# alcoholsensor.net
KiCad netlist of a schematic drawn in EAGLE
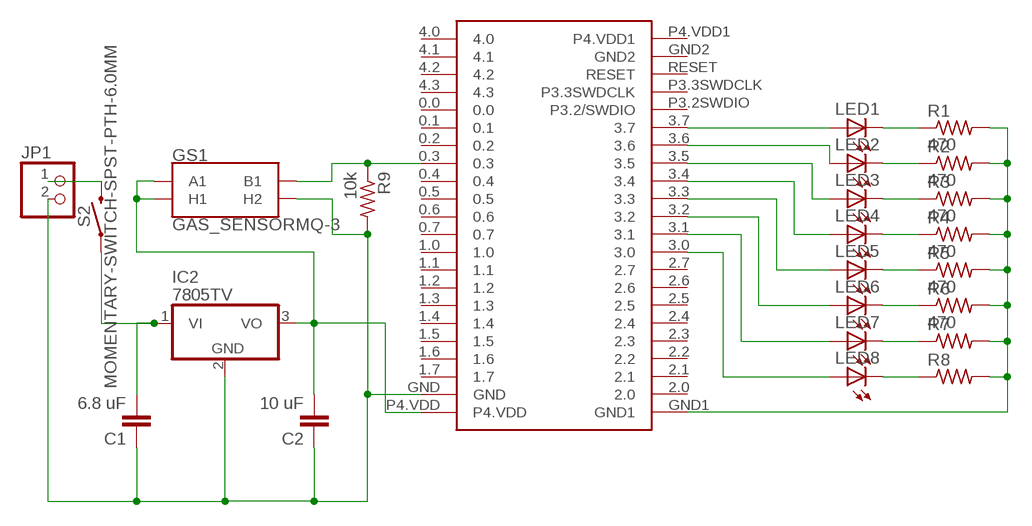
[diagram p0: schematic, sheet 1]

(export (version "E")
  (design (tool "Eeschema 10.0.6"))
  (components
    (comp (ref "C1")
      (value "6.8 uF")
      (footprint "eagle-import:C2.5-4")
      (libsource (lib "eagle-import") (part "C2.5/4"))
    )
    (comp (ref "C2")
      (value "10 uF")
      (footprint "eagle-import:C2.5-4")
      (libsource (lib "eagle-import") (part "C2.5/4"))
    )
    (comp (ref "GS1")
      (value "GAS_SENSORMQ-3")
      (footprint "eagle-import:GAS_SENSOR")
      (libsource (lib "eagle-import") (part "GAS_SENSORMQ-3"))
    )
    (comp (ref "IC2")
      (value "7805TV")
      (footprint "eagle-import:TO220V")
      (libsource (lib "eagle-import") (part "78TV05"))
    )
    (comp (ref "JP1")
      (value "PINHD-1X2")
      (footprint "eagle-import:1X02")
      (libsource (lib "eagle-import") (part "PINHD-1X2"))
    )
    (comp (ref "LED1")
      (value "LED5MM")
      (footprint "eagle-import:LED5MM")
      (libsource (lib "eagle-import") (part "LED5MM"))
    )
    (comp (ref "LED2")
      (value "LED5MM")
      (footprint "eagle-import:LED5MM")
      (libsource (lib "eagle-import") (part "LED5MM"))
    )
    (comp (ref "LED3")
      (value "LED5MM")
      (footprint "eagle-import:LED5MM")
      (libsource (lib "eagle-import") (part "LED5MM"))
    )
    (comp (ref "LED4")
      (value "LED5MM")
      (footprint "eagle-import:LED5MM")
      (libsource (lib "eagle-import") (part "LED5MM"))
    )
    (comp (ref "LED5")
      (value "LED5MM")
      (footprint "eagle-import:LED5MM")
      (libsource (lib "eagle-import") (part "LED5MM"))
    )
    (comp (ref "LED6")
      (value "LED5MM")
      (footprint "eagle-import:LED5MM")
      (libsource (lib "eagle-import") (part "LED5MM"))
    )
    (comp (ref "LED7")
      (value "LED5MM")
      (footprint "eagle-import:LED5MM")
      (libsource (lib "eagle-import") (part "LED5MM"))
    )
    (comp (ref "LED8")
      (value "LED5MM")
      (footprint "eagle-import:LED5MM")
      (libsource (lib "eagle-import") (part "LED5MM"))
    )
    (comp (ref "R1")
      (value "470")
      (footprint "eagle-import:0207_10")
      (libsource (lib "eagle-import") (part "R-US_0207/10"))
    )
    (comp (ref "R2")
      (value "470")
      (footprint "eagle-import:0207_10")
      (libsource (lib "eagle-import") (part "R-US_0207/10"))
    )
    (comp (ref "R3")
      (value "470")
      (footprint "eagle-import:0207_10")
      (libsource (lib "eagle-import") (part "R-US_0207/10"))
    )
    (comp (ref "R4")
      (value "470")
      (footprint "eagle-import:0207_10")
      (libsource (lib "eagle-import") (part "R-US_0207/10"))
    )
    (comp (ref "R5")
      (value "470")
      (footprint "eagle-import:0207_10")
      (libsource (lib "eagle-import") (part "R-US_0207/10"))
    )
    (comp (ref "R6")
      (value "470")
      (footprint "eagle-import:0207_10")
      (libsource (lib "eagle-import") (part "R-US_0207/10"))
    )
    (comp (ref "R7")
      (value "R-US_0207/10")
      (footprint "eagle-import:0207_10")
      (libsource (lib "eagle-import") (part "R-US_0207/10"))
    )
    (comp (ref "R8")
      (value "R-US_0207/10")
      (footprint "eagle-import:0207_10")
      (libsource (lib "eagle-import") (part "R-US_0207/10"))
    )
    (comp (ref "R9")
      (value "10k")
      (footprint "eagle-import:0207_10")
      (libsource (lib "eagle-import") (part "R-US_0207/10"))
    )
    (comp (ref "S2")
      (value "MOMENTARY-SWITCH-SPST-PTH-6.0MM")
      (footprint "eagle-import:TACTILE_SWITCH_PTH_6.0MM")
      (libsource (lib "eagle-import") (part "MOMENTARY-SWITCH-SPST-PTH-6.0MM"))
    )
    (comp (ref "U$1")
      (value "CY8CKIT-049")
      (footprint "eagle-import:CY8CKIT-049")
      (libsource (lib "eagle-import") (part "CY8CKIT-049"))
    )
  )
  (nets
    (net (code "1") (name "Net-(GS1-H1)") (class "Default")
      (node (ref "C2") (pin "2") (pinfunction "2_2") (pintype "passive"))
      (node (ref "GS1") (pin "A1") (pinfunction "A1_A1") (pintype "bidirectional"))
      (node (ref "GS1") (pin "HA") (pinfunction "H1_HA") (pintype "bidirectional"))
      (node (ref "IC2") (pin "3") (pinfunction "VO_3") (pintype "passive"))
      (node (ref "U$1") (pin "P4.VDD") (pinfunction "P4.VDD_P4.VDD") (pintype "bidirectional"))
    )
    (net (code "2") (name "Net-(GS1-H2)") (class "Default")
      (node (ref "C1") (pin "1") (pinfunction "1_1") (pintype "passive"))
      (node (ref "C2") (pin "1") (pinfunction "1_1") (pintype "passive"))
      (node (ref "GS1") (pin "HB") (pinfunction "H2_HB") (pintype "bidirectional"))
      (node (ref "IC2") (pin "2") (pinfunction "GND_2") (pintype "passive"))
      (node (ref "JP1") (pin "2") (pinfunction "2_2") (pintype "passive"))
      (node (ref "R9") (pin "2") (pinfunction "2_2") (pintype "passive"))
      (node (ref "U$1") (pin "GND") (pinfunction "GND_GND") (pintype "bidirectional"))
    )
    (net (code "3") (name "Net-(GS1-PadB1)") (class "Default")
      (node (ref "GS1") (pin "B1") (pinfunction "B1_B1") (pintype "bidirectional"))
      (node (ref "R9") (pin "1") (pinfunction "1_1") (pintype "passive"))
      (node (ref "U$1") (pin "0.3") (pinfunction "0.3_0.3") (pintype "bidirectional"))
    )
    (net (code "4") (name "Net-(IC2-VI)") (class "Default")
      (node (ref "C1") (pin "2") (pinfunction "2_2") (pintype "passive"))
      (node (ref "IC2") (pin "1") (pinfunction "VI_1") (pintype "input"))
      (node (ref "S2") (pin "1") (pinfunction "1_1") (pintype "passive"))
    )
    (net (code "5") (name "Net-(LED1-C)") (class "Default")
      (node (ref "LED1") (pin "K") (pinfunction "C_K") (pintype "passive"))
      (node (ref "R1") (pin "1") (pinfunction "1_1") (pintype "passive"))
    )
    (net (code "6") (name "Net-(LED1-PadA)") (class "Default")
      (node (ref "LED1") (pin "A") (pinfunction "A_A") (pintype "passive"))
      (node (ref "U$1") (pin "3.7") (pinfunction "3.7_3.7") (pintype "bidirectional"))
    )
    (net (code "7") (name "Net-(LED2-C)") (class "Default")
      (node (ref "LED2") (pin "K") (pinfunction "C_K") (pintype "passive"))
      (node (ref "R2") (pin "1") (pinfunction "1_1") (pintype "passive"))
    )
    (net (code "8") (name "Net-(LED2-PadA)") (class "Default")
      (node (ref "LED2") (pin "A") (pinfunction "A_A") (pintype "passive"))
      (node (ref "U$1") (pin "3.6") (pinfunction "3.6_3.6") (pintype "bidirectional"))
    )
    (net (code "9") (name "Net-(LED3-C)") (class "Default")
      (node (ref "LED3") (pin "K") (pinfunction "C_K") (pintype "passive"))
      (node (ref "R3") (pin "1") (pinfunction "1_1") (pintype "passive"))
    )
    (net (code "10") (name "Net-(LED3-PadA)") (class "Default")
      (node (ref "LED3") (pin "A") (pinfunction "A_A") (pintype "passive"))
      (node (ref "U$1") (pin "3.5") (pinfunction "3.5_3.5") (pintype "bidirectional"))
    )
    (net (code "11") (name "Net-(LED4-C)") (class "Default")
      (node (ref "LED4") (pin "K") (pinfunction "C_K") (pintype "passive"))
      (node (ref "R4") (pin "1") (pinfunction "1_1") (pintype "passive"))
    )
    (net (code "12") (name "Net-(LED4-PadA)") (class "Default")
      (node (ref "LED4") (pin "A") (pinfunction "A_A") (pintype "passive"))
      (node (ref "U$1") (pin "3.4") (pinfunction "3.4_3.4") (pintype "bidirectional"))
    )
    (net (code "13") (name "Net-(LED5-C)") (class "Default")
      (node (ref "LED5") (pin "K") (pinfunction "C_K") (pintype "passive"))
      (node (ref "R5") (pin "1") (pinfunction "1_1") (pintype "passive"))
    )
    (net (code "14") (name "Net-(LED5-PadA)") (class "Default")
      (node (ref "LED5") (pin "A") (pinfunction "A_A") (pintype "passive"))
      (node (ref "U$1") (pin "3.3") (pinfunction "3.3_3.3") (pintype "bidirectional"))
    )
    (net (code "15") (name "Net-(LED6-C)") (class "Default")
      (node (ref "LED6") (pin "K") (pinfunction "C_K") (pintype "passive"))
      (node (ref "R6") (pin "1") (pinfunction "1_1") (pintype "passive"))
    )
    (net (code "16") (name "Net-(LED6-PadA)") (class "Default")
      (node (ref "LED6") (pin "A") (pinfunction "A_A") (pintype "passive"))
      (node (ref "U$1") (pin "3.2") (pinfunction "3.2_3.2") (pintype "bidirectional"))
    )
    (net (code "17") (name "Net-(LED7-C)") (class "Default")
      (node (ref "LED7") (pin "K") (pinfunction "C_K") (pintype "passive"))
      (node (ref "R7") (pin "1") (pinfunction "1_1") (pintype "passive"))
    )
    (net (code "18") (name "Net-(LED7-PadA)") (class "Default")
      (node (ref "LED7") (pin "A") (pinfunction "A_A") (pintype "passive"))
      (node (ref "U$1") (pin "3.1") (pinfunction "3.1_3.1") (pintype "bidirectional"))
    )
    (net (code "19") (name "Net-(LED8-C)") (class "Default")
      (node (ref "LED8") (pin "K") (pinfunction "C_K") (pintype "passive"))
      (node (ref "R8") (pin "1") (pinfunction "1_1") (pintype "passive"))
    )
    (net (code "20") (name "Net-(LED8-PadA)") (class "Default")
      (node (ref "LED8") (pin "A") (pinfunction "A_A") (pintype "passive"))
      (node (ref "U$1") (pin "3.0") (pinfunction "3.0_3.0") (pintype "bidirectional"))
    )
    (net (code "21") (name "Net-(R1-Pad2)") (class "Default")
      (node (ref "R1") (pin "2") (pinfunction "2_2") (pintype "passive"))
      (node (ref "R2") (pin "2") (pinfunction "2_2") (pintype "passive"))
      (node (ref "R3") (pin "2") (pinfunction "2_2") (pintype "passive"))
      (node (ref "R4") (pin "2") (pinfunction "2_2") (pintype "passive"))
      (node (ref "R5") (pin "2") (pinfunction "2_2") (pintype "passive"))
      (node (ref "R6") (pin "2") (pinfunction "2_2") (pintype "passive"))
      (node (ref "R7") (pin "2") (pinfunction "2_2") (pintype "passive"))
      (node (ref "R8") (pin "2") (pinfunction "2_2") (pintype "passive"))
      (node (ref "U$1") (pin "GND1") (pinfunction "GND1_GND1") (pintype "bidirectional"))
    )
    (net (code "22") (name "Net-(S2-2)") (class "Default")
      (node (ref "JP1") (pin "1") (pinfunction "1_1") (pintype "passive"))
      (node (ref "S2") (pin "3") (pinfunction "2_3") (pintype "passive"))
    )
    (net (code "23") (name "unconnected-(U$1-P3.2{slash}SWDIO-PadP3.2SWDIO)") (class "Default")
      (node (ref "U$1") (pin "P3.2SWDIO") (pinfunction "P3.2/SWDIO_P3.2SWDIO") (pintype "bidirectional"))
    )
    (net (code "24") (name "unconnected-(U$1-Pad0.0)") (class "Default")
      (node (ref "U$1") (pin "0.0") (pinfunction "0.0_0.0") (pintype "bidirectional"))
    )
    (net (code "25") (name "unconnected-(U$1-Pad0.1)") (class "Default")
      (node (ref "U$1") (pin "0.1") (pinfunction "0.1_0.1") (pintype "bidirectional"))
    )
    (net (code "26") (name "unconnected-(U$1-Pad0.2)") (class "Default")
      (node (ref "U$1") (pin "0.2") (pinfunction "0.2_0.2") (pintype "bidirectional"))
    )
    (net (code "27") (name "unconnected-(U$1-Pad0.4)") (class "Default")
      (node (ref "U$1") (pin "0.4") (pinfunction "0.4_0.4") (pintype "bidirectional"))
    )
    (net (code "28") (name "unconnected-(U$1-Pad0.5)") (class "Default")
      (node (ref "U$1") (pin "0.5") (pinfunction "0.5_0.5") (pintype "bidirectional"))
    )
    (net (code "29") (name "unconnected-(U$1-Pad0.6)") (class "Default")
      (node (ref "U$1") (pin "0.6") (pinfunction "0.6_0.6") (pintype "bidirectional"))
    )
    (net (code "30") (name "unconnected-(U$1-Pad0.7)") (class "Default")
      (node (ref "U$1") (pin "0.7") (pinfunction "0.7_0.7") (pintype "bidirectional"))
    )
    (net (code "31") (name "unconnected-(U$1-Pad1.0)") (class "Default")
      (node (ref "U$1") (pin "1.0") (pinfunction "1.0_1.0") (pintype "bidirectional"))
    )
    (net (code "32") (name "unconnected-(U$1-Pad1.1)") (class "Default")
      (node (ref "U$1") (pin "1.1") (pinfunction "1.1_1.1") (pintype "bidirectional"))
    )
    (net (code "33") (name "unconnected-(U$1-Pad1.2)") (class "Default")
      (node (ref "U$1") (pin "1.2") (pinfunction "1.2_1.2") (pintype "bidirectional"))
    )
    (net (code "34") (name "unconnected-(U$1-Pad1.3)") (class "Default")
      (node (ref "U$1") (pin "1.3") (pinfunction "1.3_1.3") (pintype "bidirectional"))
    )
    (net (code "35") (name "unconnected-(U$1-Pad1.4)") (class "Default")
      (node (ref "U$1") (pin "1.4") (pinfunction "1.4_1.4") (pintype "bidirectional"))
    )
    (net (code "36") (name "unconnected-(U$1-Pad1.5)") (class "Default")
      (node (ref "U$1") (pin "1.5") (pinfunction "1.5_1.5") (pintype "bidirectional"))
    )
    (net (code "37") (name "unconnected-(U$1-Pad1.6)") (class "Default")
      (node (ref "U$1") (pin "1.6") (pinfunction "1.6_1.6") (pintype "bidirectional"))
    )
    (net (code "38") (name "unconnected-(U$1-Pad1.7)") (class "Default")
      (node (ref "U$1") (pin "1.7") (pinfunction "1.7_1.7") (pintype "bidirectional"))
    )
    (net (code "39") (name "unconnected-(U$1-Pad2.0)") (class "Default")
      (node (ref "U$1") (pin "2.0") (pinfunction "2.0_2.0") (pintype "bidirectional"))
    )
    (net (code "40") (name "unconnected-(U$1-Pad2.1)") (class "Default")
      (node (ref "U$1") (pin "2.1") (pinfunction "2.1_2.1") (pintype "bidirectional"))
    )
    (net (code "41") (name "unconnected-(U$1-Pad2.2)") (class "Default")
      (node (ref "U$1") (pin "2.2") (pinfunction "2.2_2.2") (pintype "bidirectional"))
    )
    (net (code "42") (name "unconnected-(U$1-Pad2.3)") (class "Default")
      (node (ref "U$1") (pin "2.3") (pinfunction "2.3_2.3") (pintype "bidirectional"))
    )
    (net (code "43") (name "unconnected-(U$1-Pad2.4)") (class "Default")
      (node (ref "U$1") (pin "2.4") (pinfunction "2.4_2.4") (pintype "bidirectional"))
    )
    (net (code "44") (name "unconnected-(U$1-Pad2.5)") (class "Default")
      (node (ref "U$1") (pin "2.5") (pinfunction "2.5_2.5") (pintype "bidirectional"))
    )
    (net (code "45") (name "unconnected-(U$1-Pad2.6)") (class "Default")
      (node (ref "U$1") (pin "2.6") (pinfunction "2.6_2.6") (pintype "bidirectional"))
    )
    (net (code "46") (name "unconnected-(U$1-Pad2.7)") (class "Default")
      (node (ref "U$1") (pin "2.7") (pinfunction "2.7_2.7") (pintype "bidirectional"))
    )
    (net (code "47") (name "unconnected-(U$1-Pad4.0)") (class "Default")
      (node (ref "U$1") (pin "4.0") (pinfunction "4.0_4.0") (pintype "bidirectional"))
    )
    (net (code "48") (name "unconnected-(U$1-Pad4.1)") (class "Default")
      (node (ref "U$1") (pin "4.1") (pinfunction "4.1_4.1") (pintype "bidirectional"))
    )
    (net (code "49") (name "unconnected-(U$1-Pad4.2)") (class "Default")
      (node (ref "U$1") (pin "4.2") (pinfunction "4.2_4.2") (pintype "bidirectional"))
    )
    (net (code "50") (name "unconnected-(U$1-Pad4.3)") (class "Default")
      (node (ref "U$1") (pin "4.3") (pinfunction "4.3_4.3") (pintype "bidirectional"))
    )
    (net (code "51") (name "unconnected-(U$1-PadGND2)") (class "Default")
      (node (ref "U$1") (pin "GND2") (pinfunction "GND2_GND2") (pintype "bidirectional"))
    )
    (net (code "52") (name "unconnected-(U$1-PadP3.3SWDCLK)") (class "Default")
      (node (ref "U$1") (pin "P3.3SWDCLK") (pinfunction "P3.3SWDCLK_P3.3SWDCLK") (pintype "bidirectional"))
    )
    (net (code "53") (name "unconnected-(U$1-PadP4.VDD1)") (class "Default")
      (node (ref "U$1") (pin "P4.VDD1") (pinfunction "P4.VDD1_P4.VDD1") (pintype "bidirectional"))
    )
    (net (code "54") (name "unconnected-(U$1-PadRESET)") (class "Default")
      (node (ref "U$1") (pin "RESET") (pinfunction "RESET_RESET") (pintype "bidirectional"))
    )
  )
)
